# CLKB_clocking_fpga.net
KiCad netlist of a schematic drawn in Altium Designer
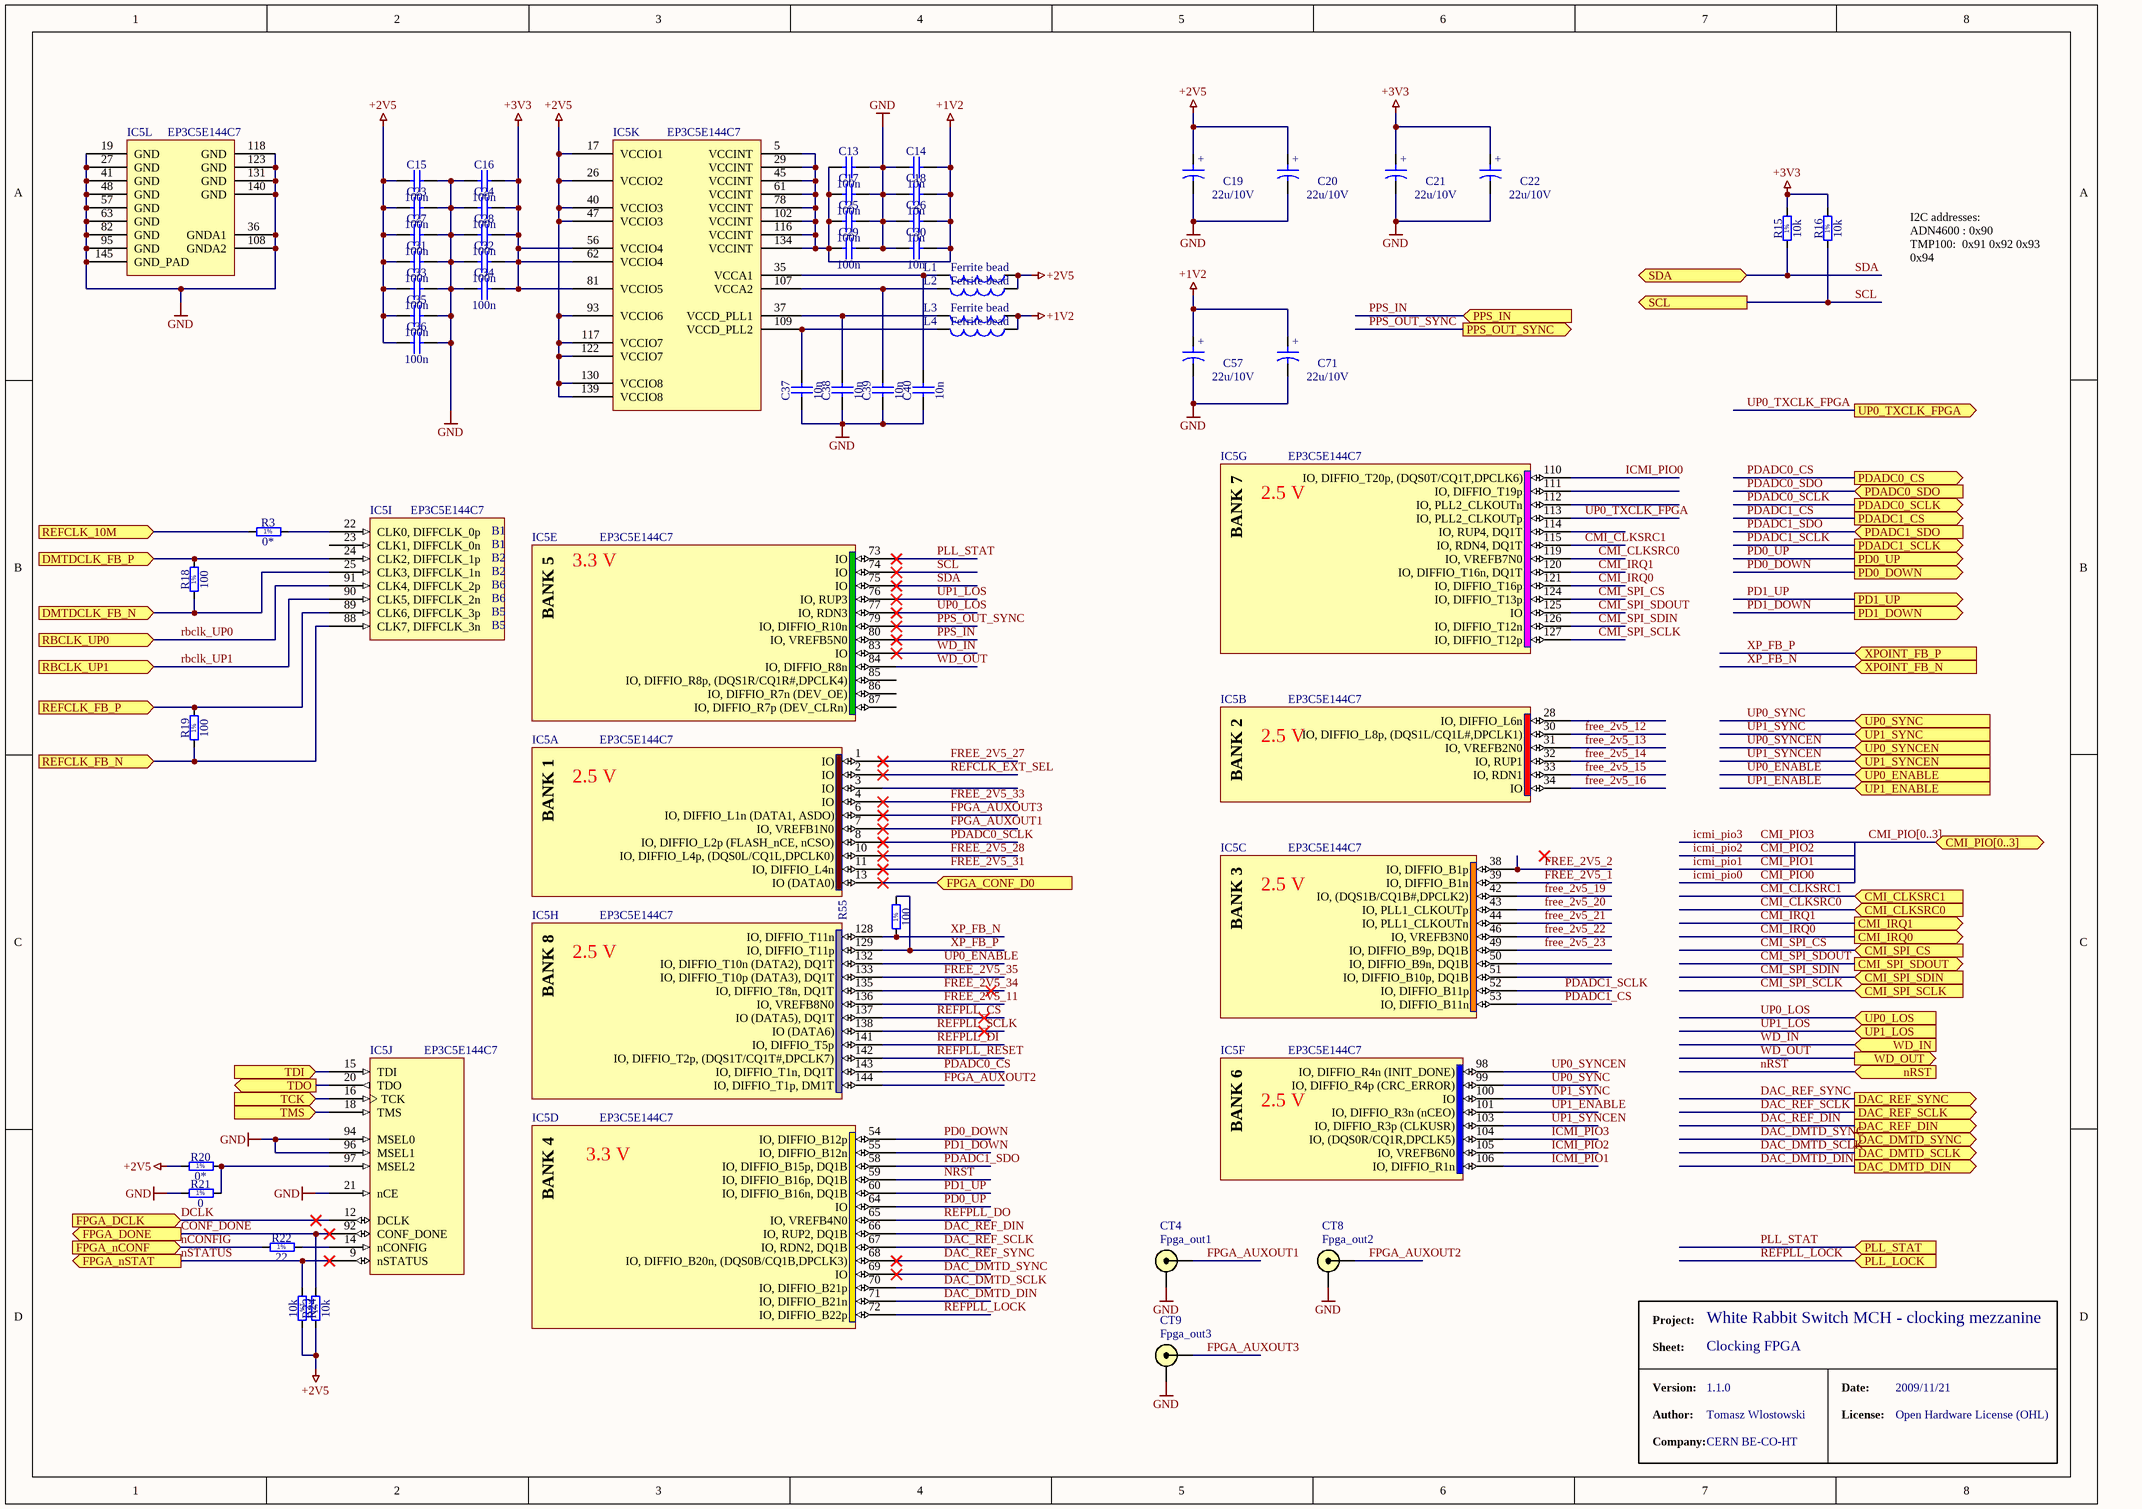
[diagram p0: CLKB_clocking_fpga.SchDoc]

(export (version "E")
  (design (tool "Eeschema 10.0.6"))
  (components
    (comp (ref "C13")
      (value "100n")
      (footprint "CAPC1608X87N")
      (description "Non-polarised capacitor")
      (fields
        (field (name "PART NUMBER") "CC0603_100NF_50V_10%_X7R")
        (field (name "VOLTAGE") "50V")
        (field (name "AUTHOR") "CERN DEM JLC")
      )
      (libsource (lib "Capacitors") (part "Capacitor - non polarized"))
    )
    (comp (ref "C14")
      (value "10n")
      (footprint "CAPC1608X87N")
      (description "Non-polarised capacitor")
      (fields
        (field (name "PART NUMBER") "CC0603_10NF_50V_10%_X7R")
        (field (name "VOLTAGE") "50V")
        (field (name "AUTHOR") "CERN DEM JLC")
      )
      (libsource (lib "Capacitors") (part "Capacitor - non polarized"))
    )
    (comp (ref "C15")
      (value "100n")
      (footprint "CAPC1608X87N")
      (description "Non-polarised capacitor")
      (fields
        (field (name "PART NUMBER") "CC0603_100NF_50V_10%_X7R")
        (field (name "VOLTAGE") "50V")
        (field (name "AUTHOR") "CERN DEM JLC")
      )
      (libsource (lib "Capacitors") (part "Capacitor - non polarized"))
    )
    (comp (ref "C16")
      (value "100n")
      (footprint "CAPC1608X87N")
      (description "Non-polarised capacitor")
      (fields
        (field (name "PART NUMBER") "CC0603_100NF_50V_10%_X7R")
        (field (name "VOLTAGE") "50V")
        (field (name "AUTHOR") "CERN DEM JLC")
      )
      (libsource (lib "Capacitors") (part "Capacitor - non polarized"))
    )
    (comp (ref "C17")
      (value "100n")
      (footprint "CAPC1608X87N")
      (description "Non-polarised capacitor")
      (fields
        (field (name "PART NUMBER") "CC0603_100NF_50V_10%_X7R")
        (field (name "VOLTAGE") "50V")
        (field (name "AUTHOR") "CERN DEM JLC")
      )
      (libsource (lib "Capacitors") (part "Capacitor - non polarized"))
    )
    (comp (ref "C18")
      (value "10n")
      (footprint "CAPC1608X87N")
      (description "Non-polarised capacitor")
      (fields
        (field (name "PART NUMBER") "CC0603_10NF_50V_10%_X7R")
        (field (name "VOLTAGE") "50V")
        (field (name "AUTHOR") "CERN DEM JLC")
      )
      (libsource (lib "Capacitors") (part "Capacitor - non polarized"))
    )
    (comp (ref "C19")
      (value "22u/10V")
      (footprint "CAPMP3216X180N")
      (description "Polarised capacitor")
      (fields
        (field (name "PART NUMBER") "CTE3216-18_22UF_10V_10%")
        (field (name "VOLTAGE") "10V")
        (field (name "AUTHOR") "CERN DEM JLC")
      )
      (libsource (lib "Capacitors") (part "Capacitor - polarized"))
    )
    (comp (ref "C20")
      (value "22u/10V")
      (footprint "CAPMP3216X180N")
      (description "Polarised capacitor")
      (fields
        (field (name "PART NUMBER") "CTE3216-18_22UF_10V_10%")
        (field (name "VOLTAGE") "10V")
        (field (name "AUTHOR") "CERN DEM JLC")
      )
      (libsource (lib "Capacitors") (part "Capacitor - polarized"))
    )
    (comp (ref "C21")
      (value "22u/10V")
      (footprint "CAPMP3216X180N")
      (description "Polarised capacitor")
      (fields
        (field (name "PART NUMBER") "CTE3216-18_22UF_10V_10%")
        (field (name "VOLTAGE") "10V")
        (field (name "AUTHOR") "CERN DEM JLC")
      )
      (libsource (lib "Capacitors") (part "Capacitor - polarized"))
    )
    (comp (ref "C22")
      (value "22u/10V")
      (footprint "CAPMP3216X180N")
      (description "Polarised capacitor")
      (fields
        (field (name "PART NUMBER") "CTE3216-18_22UF_10V_10%")
        (field (name "VOLTAGE") "10V")
        (field (name "AUTHOR") "CERN DEM JLC")
      )
      (libsource (lib "Capacitors") (part "Capacitor - polarized"))
    )
    (comp (ref "C23")
      (value "100n")
      (footprint "CAPC1608X87N")
      (description "Non-polarised capacitor")
      (fields
        (field (name "PART NUMBER") "CC0603_100NF_50V_10%_X7R")
        (field (name "VOLTAGE") "50V")
        (field (name "AUTHOR") "CERN DEM JLC")
      )
      (libsource (lib "Capacitors") (part "Capacitor - non polarized"))
    )
    (comp (ref "C24")
      (value "100n")
      (footprint "CAPC1608X87N")
      (description "Non-polarised capacitor")
      (fields
        (field (name "PART NUMBER") "CC0603_100NF_50V_10%_X7R")
        (field (name "VOLTAGE") "50V")
        (field (name "AUTHOR") "CERN DEM JLC")
      )
      (libsource (lib "Capacitors") (part "Capacitor - non polarized"))
    )
    (comp (ref "C25")
      (value "100n")
      (footprint "CAPC1608X87N")
      (description "Non-polarised capacitor")
      (fields
        (field (name "PART NUMBER") "CC0603_100NF_50V_10%_X7R")
        (field (name "VOLTAGE") "50V")
        (field (name "AUTHOR") "CERN DEM JLC")
      )
      (libsource (lib "Capacitors") (part "Capacitor - non polarized"))
    )
    (comp (ref "C26")
      (value "10n")
      (footprint "CAPC1608X87N")
      (description "Non-polarised capacitor")
      (fields
        (field (name "PART NUMBER") "CC0603_10NF_50V_10%_X7R")
        (field (name "VOLTAGE") "50V")
        (field (name "AUTHOR") "CERN DEM JLC")
      )
      (libsource (lib "Capacitors") (part "Capacitor - non polarized"))
    )
    (comp (ref "C27")
      (value "100n")
      (footprint "CAPC1608X87N")
      (description "Non-polarised capacitor")
      (fields
        (field (name "PART NUMBER") "CC0603_100NF_50V_10%_X7R")
        (field (name "VOLTAGE") "50V")
        (field (name "AUTHOR") "CERN DEM JLC")
      )
      (libsource (lib "Capacitors") (part "Capacitor - non polarized"))
    )
    (comp (ref "C28")
      (value "100n")
      (footprint "CAPC1608X87N")
      (description "Non-polarised capacitor")
      (fields
        (field (name "PART NUMBER") "CC0603_100NF_50V_10%_X7R")
        (field (name "VOLTAGE") "50V")
        (field (name "AUTHOR") "CERN DEM JLC")
      )
      (libsource (lib "Capacitors") (part "Capacitor - non polarized"))
    )
    (comp (ref "C29")
      (value "100n")
      (footprint "CAPC1608X87N")
      (description "Non-polarised capacitor")
      (fields
        (field (name "PART NUMBER") "CC0603_100NF_50V_10%_X7R")
        (field (name "VOLTAGE") "50V")
        (field (name "AUTHOR") "CERN DEM JLC")
      )
      (libsource (lib "Capacitors") (part "Capacitor - non polarized"))
    )
    (comp (ref "C30")
      (value "10n")
      (footprint "CAPC1608X87N")
      (description "Non-polarised capacitor")
      (fields
        (field (name "PART NUMBER") "CC0603_10NF_50V_10%_X7R")
        (field (name "VOLTAGE") "50V")
        (field (name "AUTHOR") "CERN DEM JLC")
      )
      (libsource (lib "Capacitors") (part "Capacitor - non polarized"))
    )
    (comp (ref "C31")
      (value "100n")
      (footprint "CAPC1608X87N")
      (description "Non-polarised capacitor")
      (fields
        (field (name "PART NUMBER") "CC0603_100NF_50V_10%_X7R")
        (field (name "VOLTAGE") "50V")
        (field (name "AUTHOR") "CERN DEM JLC")
      )
      (libsource (lib "Capacitors") (part "Capacitor - non polarized"))
    )
    (comp (ref "C32")
      (value "100n")
      (footprint "CAPC1608X87N")
      (description "Non-polarised capacitor")
      (fields
        (field (name "PART NUMBER") "CC0603_100NF_50V_10%_X7R")
        (field (name "VOLTAGE") "50V")
        (field (name "AUTHOR") "CERN DEM JLC")
      )
      (libsource (lib "Capacitors") (part "Capacitor - non polarized"))
    )
    (comp (ref "C33")
      (value "100n")
      (footprint "CAPC1608X87N")
      (description "Non-polarised capacitor")
      (fields
        (field (name "PART NUMBER") "CC0603_100NF_50V_10%_X7R")
        (field (name "VOLTAGE") "50V")
        (field (name "AUTHOR") "CERN DEM JLC")
      )
      (libsource (lib "Capacitors") (part "Capacitor - non polarized"))
    )
    (comp (ref "C34")
      (value "100n")
      (footprint "CAPC1608X87N")
      (description "Non-polarised capacitor")
      (fields
        (field (name "PART NUMBER") "CC0603_100NF_50V_10%_X7R")
        (field (name "VOLTAGE") "50V")
        (field (name "AUTHOR") "CERN DEM JLC")
      )
      (libsource (lib "Capacitors") (part "Capacitor - non polarized"))
    )
    (comp (ref "C35")
      (value "100n")
      (footprint "CAPC1608X87N")
      (description "Non-polarised capacitor")
      (fields
        (field (name "PART NUMBER") "CC0603_100NF_50V_10%_X7R")
        (field (name "VOLTAGE") "50V")
        (field (name "AUTHOR") "CERN DEM JLC")
      )
      (libsource (lib "Capacitors") (part "Capacitor - non polarized"))
    )
    (comp (ref "C36")
      (value "100n")
      (footprint "CAPC1608X87N")
      (description "Non-polarised capacitor")
      (fields
        (field (name "PART NUMBER") "CC0603_100NF_50V_10%_X7R")
        (field (name "VOLTAGE") "50V")
        (field (name "AUTHOR") "CERN DEM JLC")
      )
      (libsource (lib "Capacitors") (part "Capacitor - non polarized"))
    )
    (comp (ref "C37")
      (value "10n")
      (footprint "CAPC1608X87N")
      (description "Non-polarised capacitor")
      (fields
        (field (name "PART NUMBER") "CC0603_10NF_50V_10%_X7R")
        (field (name "VOLTAGE") "50V")
        (field (name "AUTHOR") "CERN DEM JLC")
      )
      (libsource (lib "Capacitors") (part "Capacitor - non polarized"))
    )
    (comp (ref "C38")
      (value "10n")
      (footprint "CAPC1608X87N")
      (description "Non-polarised capacitor")
      (fields
        (field (name "PART NUMBER") "CC0603_10NF_50V_10%_X7R")
        (field (name "VOLTAGE") "50V")
        (field (name "AUTHOR") "CERN DEM JLC")
      )
      (libsource (lib "Capacitors") (part "Capacitor - non polarized"))
    )
    (comp (ref "C39")
      (value "10n")
      (footprint "CAPC1608X87N")
      (description "Non-polarised capacitor")
      (fields
        (field (name "PART NUMBER") "CC0603_10NF_50V_10%_X7R")
        (field (name "VOLTAGE") "50V")
        (field (name "AUTHOR") "CERN DEM JLC")
      )
      (libsource (lib "Capacitors") (part "Capacitor - non polarized"))
    )
    (comp (ref "C40")
      (value "10n")
      (footprint "CAPC1608X87N")
      (description "Non-polarised capacitor")
      (fields
        (field (name "PART NUMBER") "CC0603_10NF_50V_10%_X7R")
        (field (name "VOLTAGE") "50V")
        (field (name "AUTHOR") "CERN DEM JLC")
      )
      (libsource (lib "Capacitors") (part "Capacitor - non polarized"))
    )
    (comp (ref "C57")
      (value "22u/10V")
      (footprint "CAPMP3216X180N")
      (description "Polarised capacitor")
      (fields
        (field (name "PART NUMBER") "CTE3216-18_22UF_10V_10%")
        (field (name "VOLTAGE") "10V")
        (field (name "AUTHOR") "CERN DEM JLC")
      )
      (libsource (lib "Capacitors") (part "Capacitor - polarized"))
    )
    (comp (ref "C71")
      (value "22u/10V")
      (footprint "CAPMP3216X180N")
      (description "Polarised capacitor")
      (fields
        (field (name "PART NUMBER") "CTE3216-18_22UF_10V_10%")
        (field (name "VOLTAGE") "10V")
        (field (name "AUTHOR") "CERN DEM JLC")
      )
      (libsource (lib "Capacitors") (part "Capacitor - polarized"))
    )
    (comp (ref "CT4")
      (value "Fpga_out1")
      (footprint "CON_UFL_HIROSE_RECEPTACLE")
      (description "UFL connector testpoint")
      (libsource (lib "wr_switch") (part "CON_TESTPOINT_UFL"))
    )
    (comp (ref "CT8")
      (value "Fpga_out2")
      (footprint "CON_UFL_HIROSE_RECEPTACLE")
      (description "UFL connector testpoint")
      (libsource (lib "wr_switch") (part "CON_TESTPOINT_UFL"))
    )
    (comp (ref "CT9")
      (value "Fpga_out3")
      (footprint "CON_UFL_HIROSE_RECEPTACLE")
      (description "UFL connector testpoint")
      (libsource (lib "wr_switch") (part "CON_TESTPOINT_UFL"))
    )
    (comp (ref "IC5")
      (value "EP3C5E144C7")
      (footprint "EQFP144_N")
      (description "Cyclone III Family FPGA, 94 I/O Pins, 4 PLLs, 144-Pin EQFP, Speed Grade 7, Commercial Grade")
      (fields (field (name "PUBLISHER") "Altium Limited"))
      (libsource (lib "wr_switch") (part "EP3C5E144C7"))
    )
    (comp (ref "L1")
      (value "Ferrite bead")
      (footprint "L0603")
      (fields (field (name "PUBLISHER") "Altium Limited"))
      (libsource (lib "Miscellaneous Devices") (part "Inductor"))
    )
    (comp (ref "L2")
      (value "Ferrite bead")
      (footprint "L0603")
      (fields (field (name "PUBLISHER") "Altium Limited"))
      (libsource (lib "Miscellaneous Devices") (part "Inductor"))
    )
    (comp (ref "L3")
      (value "Ferrite bead")
      (footprint "L0603")
      (fields (field (name "PUBLISHER") "Altium Limited"))
      (libsource (lib "Miscellaneous Devices") (part "Inductor"))
    )
    (comp (ref "L4")
      (value "Ferrite bead")
      (footprint "L0603")
      (fields (field (name "PUBLISHER") "Altium Limited"))
      (libsource (lib "Miscellaneous Devices") (part "Inductor"))
    )
    (comp (ref "R3")
      (value "0*")
      (footprint "RESC1608X55N")
      (description "Resistor - 1%")
      (fields
        (field (name "PART NUMBER") "R0603_0R_JUMPER")
        (field (name "MANUFACTURER") "GENERIC")
        (field (name "AUTHOR") "CERN DEM JLC")
      )
      (libsource (lib "Resistors") (part "Resistor - 1%"))
    )
    (comp (ref "R15")
      (value "10k")
      (footprint "RESC1608X55N")
      (description "Resistor - 1%")
      (fields
        (field (name "PART NUMBER") "R0603_10K_1%_0.1W_100PPM")
        (field (name "POWER") "0.1W")
        (field (name "AUTHOR") "CERN DEM JLC")
      )
      (libsource (lib "Resistors") (part "Resistor - 1%"))
    )
    (comp (ref "R16")
      (value "10k")
      (footprint "RESC1608X55N")
      (description "Resistor - 1%")
      (fields
        (field (name "PART NUMBER") "R0603_10K_1%_0.1W_100PPM")
        (field (name "POWER") "0.1W")
        (field (name "AUTHOR") "CERN DEM JLC")
      )
      (libsource (lib "Resistors") (part "Resistor - 1%"))
    )
    (comp (ref "R18")
      (value "100")
      (footprint "RESC1608X55N")
      (description "Resistor - 1%")
      (fields
        (field (name "PART NUMBER") "R0603_100R_1%_0.1W_100PPM")
        (field (name "POWER") "0.1W")
        (field (name "AUTHOR") "CERN DEM JLC")
      )
      (libsource (lib "Resistors") (part "Resistor - 1%"))
    )
    (comp (ref "R19")
      (value "100")
      (footprint "RESC1608X55N")
      (description "Resistor - 1%")
      (fields
        (field (name "PART NUMBER") "R0603_100R_1%_0.1W_100PPM")
        (field (name "POWER") "0.1W")
        (field (name "AUTHOR") "CERN DEM JLC")
      )
      (libsource (lib "Resistors") (part "Resistor - 1%"))
    )
    (comp (ref "R20")
      (value "0*")
      (footprint "RESC1608X55N")
      (description "Resistor - 1%")
      (fields
        (field (name "PART NUMBER") "R0603_0R_JUMPER")
        (field (name "MANUFACTURER") "GENERIC")
        (field (name "AUTHOR") "CERN DEM JLC")
      )
      (libsource (lib "Resistors") (part "Resistor - 1%"))
    )
    (comp (ref "R21")
      (value "0")
      (footprint "RESC1608X55N")
      (description "Resistor - 1%")
      (fields
        (field (name "PART NUMBER") "R0603_0R_JUMPER")
        (field (name "MANUFACTURER") "GENERIC")
        (field (name "AUTHOR") "CERN DEM JLC")
      )
      (libsource (lib "Resistors") (part "Resistor - 1%"))
    )
    (comp (ref "R22")
      (value "22")
      (footprint "RESC1608X55N")
      (description "Resistor - 1%")
      (fields
        (field (name "PART NUMBER") "R0603_22R_1%_0.1W_100PPM")
        (field (name "POWER") "0.1W")
        (field (name "AUTHOR") "CERN DEM JLC")
      )
      (libsource (lib "Resistors") (part "Resistor - 1%"))
    )
    (comp (ref "R23")
      (value "10k")
      (footprint "RESC1608X55N")
      (description "Resistor - 1%")
      (fields
        (field (name "PART NUMBER") "R0603_10K_1%_0.1W_100PPM")
        (field (name "POWER") "0.1W")
        (field (name "AUTHOR") "CERN DEM JLC")
      )
      (libsource (lib "Resistors") (part "Resistor - 1%"))
    )
    (comp (ref "R24")
      (value "10k")
      (footprint "RESC1608X55N")
      (description "Resistor - 1%")
      (fields
        (field (name "PART NUMBER") "R0603_10K_1%_0.1W_100PPM")
        (field (name "POWER") "0.1W")
        (field (name "AUTHOR") "CERN DEM JLC")
      )
      (libsource (lib "Resistors") (part "Resistor - 1%"))
    )
    (comp (ref "R55")
      (value "100")
      (footprint "RESC1608X55N")
      (description "Resistor - 1%")
      (fields
        (field (name "PART NUMBER") "R0603_100R_1%_0.1W_100PPM")
        (field (name "POWER") "0.1W")
        (field (name "AUTHOR") "CERN DEM JLC")
      )
      (libsource (lib "Resistors") (part "Resistor - 1%"))
    )
  )
  (nets
    (net (code "1") (name "+1V2") (class "Default")
      (node (ref "C13") (pin "1") (pinfunction "1_1") (pintype "passive"))
      (node (ref "C14") (pin "2") (pinfunction "2_2") (pintype "passive"))
      (node (ref "C17") (pin "1") (pinfunction "1_1") (pintype "passive"))
      (node (ref "C18") (pin "2") (pinfunction "2_2") (pintype "passive"))
      (node (ref "C25") (pin "1") (pinfunction "1_1") (pintype "passive"))
      (node (ref "C26") (pin "2") (pinfunction "2_2") (pintype "passive"))
      (node (ref "C29") (pin "1") (pinfunction "1_1") (pintype "passive"))
      (node (ref "C30") (pin "2") (pinfunction "2_2") (pintype "passive"))
      (node (ref "C57") (pin "1") (pinfunction "1_1") (pintype "passive"))
      (node (ref "C71") (pin "1") (pinfunction "1_1") (pintype "passive"))
      (node (ref "IC5") (pin "102") (pinfunction "VCCINT_102") (pintype "power_in"))
      (node (ref "IC5") (pin "116") (pinfunction "VCCINT_116") (pintype "power_in"))
      (node (ref "IC5") (pin "134") (pinfunction "VCCINT_134") (pintype "power_in"))
      (node (ref "IC5") (pin "29") (pinfunction "VCCINT_29") (pintype "power_in"))
      (node (ref "IC5") (pin "45") (pinfunction "VCCINT_45") (pintype "power_in"))
      (node (ref "IC5") (pin "5") (pinfunction "VCCINT_5") (pintype "power_in"))
      (node (ref "IC5") (pin "61") (pinfunction "VCCINT_61") (pintype "power_in"))
      (node (ref "IC5") (pin "78") (pinfunction "VCCINT_78") (pintype "power_in"))
      (node (ref "L3") (pin "1") (pinfunction "1_1") (pintype "passive"))
      (node (ref "L4") (pin "1") (pinfunction "1_1") (pintype "passive"))
    )
    (net (code "2") (name "+2V5") (class "Default")
      (node (ref "C15") (pin "1") (pinfunction "1_1") (pintype "passive"))
      (node (ref "C19") (pin "1") (pinfunction "1_1") (pintype "passive"))
      (node (ref "C20") (pin "1") (pinfunction "1_1") (pintype "passive"))
      (node (ref "C23") (pin "1") (pinfunction "1_1") (pintype "passive"))
      (node (ref "C27") (pin "1") (pinfunction "1_1") (pintype "passive"))
      (node (ref "C31") (pin "1") (pinfunction "1_1") (pintype "passive"))
      (node (ref "C33") (pin "1") (pinfunction "1_1") (pintype "passive"))
      (node (ref "C35") (pin "1") (pinfunction "1_1") (pintype "passive"))
      (node (ref "C36") (pin "1") (pinfunction "1_1") (pintype "passive"))
      (node (ref "IC5") (pin "117") (pinfunction "VCCIO7_117") (pintype "power_in"))
      (node (ref "IC5") (pin "122") (pinfunction "VCCIO7_122") (pintype "power_in"))
      (node (ref "IC5") (pin "130") (pinfunction "VCCIO8_130") (pintype "power_in"))
      (node (ref "IC5") (pin "139") (pinfunction "VCCIO8_139") (pintype "power_in"))
      (node (ref "IC5") (pin "17") (pinfunction "VCCIO1_17") (pintype "power_in"))
      (node (ref "IC5") (pin "26") (pinfunction "VCCIO2_26") (pintype "power_in"))
      (node (ref "IC5") (pin "40") (pinfunction "VCCIO3_40") (pintype "power_in"))
      (node (ref "IC5") (pin "47") (pinfunction "VCCIO3_47") (pintype "power_in"))
      (node (ref "IC5") (pin "93") (pinfunction "VCCIO6_93") (pintype "power_in"))
      (node (ref "L1") (pin "1") (pinfunction "1_1") (pintype "passive"))
      (node (ref "L2") (pin "1") (pinfunction "1_1") (pintype "passive"))
      (node (ref "R20") (pin "1") (pinfunction "1_1") (pintype "passive"))
      (node (ref "R23") (pin "1") (pinfunction "1_1") (pintype "passive"))
      (node (ref "R24") (pin "2") (pinfunction "2_2") (pintype "passive"))
    )
    (net (code "3") (name "+3V3") (class "Default")
      (node (ref "C16") (pin "2") (pinfunction "2_2") (pintype "passive"))
      (node (ref "C21") (pin "1") (pinfunction "1_1") (pintype "passive"))
      (node (ref "C22") (pin "1") (pinfunction "1_1") (pintype "passive"))
      (node (ref "C24") (pin "2") (pinfunction "2_2") (pintype "passive"))
      (node (ref "C28") (pin "2") (pinfunction "2_2") (pintype "passive"))
      (node (ref "C32") (pin "2") (pinfunction "2_2") (pintype "passive"))
      (node (ref "C34") (pin "2") (pinfunction "2_2") (pintype "passive"))
      (node (ref "IC5") (pin "56") (pinfunction "VCCIO4_56") (pintype "power_in"))
      (node (ref "IC5") (pin "62") (pinfunction "VCCIO4_62") (pintype "power_in"))
      (node (ref "IC5") (pin "81") (pinfunction "VCCIO5_81") (pintype "power_in"))
      (node (ref "R15") (pin "2") (pinfunction "2_2") (pintype "passive"))
      (node (ref "R16") (pin "2") (pinfunction "2_2") (pintype "passive"))
    )
    (net (code "4") (name "/CMI_CLKSRC0") (class "Default")
      (node (ref "IC5") (pin "119") (pinfunction "IO,_VREFB7N0_119") (pintype "bidirectional"))
    )
    (net (code "5") (name "/CMI_CLKSRC1") (class "Default")
      (node (ref "IC5") (pin "115") (pinfunction "IO,_RDN4,_DQ1T_115") (pintype "bidirectional"))
    )
    (net (code "6") (name "/CMI_IRQ0") (class "Default")
      (node (ref "IC5") (pin "121") (pinfunction "IO,_DIFFIO_T16p_121") (pintype "bidirectional"))
    )
    (net (code "7") (name "/CMI_IRQ1") (class "Default")
      (node (ref "IC5") (pin "120") (pinfunction "IO,_DIFFIO_T16n,_DQ1T_120") (pintype "bidirectional"))
    )
    (net (code "13") (name "/CMI_SPI_CS") (class "Default")
      (node (ref "IC5") (pin "124") (pinfunction "IO,_DIFFIO_T13p_124") (pintype "bidirectional"))
    )
    (net (code "14") (name "/CMI_SPI_SCLK") (class "Default")
      (node (ref "IC5") (pin "127") (pinfunction "IO,_DIFFIO_T12p_127") (pintype "bidirectional"))
    )
    (net (code "15") (name "/CMI_SPI_SDIN") (class "Default")
      (node (ref "IC5") (pin "126") (pinfunction "IO,_DIFFIO_T12n_126") (pintype "bidirectional"))
    )
    (net (code "16") (name "/CMI_SPI_SDOUT") (class "Default")
      (node (ref "IC5") (pin "125") (pinfunction "IO_125") (pintype "bidirectional"))
    )
    (net (code "17") (name "/CONF_DONE") (class "Default")
      (node (ref "IC5") (pin "92") (pinfunction "CONF_DONE_92") (pintype "bidirectional"))
      (node (ref "R23") (pin "2") (pinfunction "2_2") (pintype "passive"))
    )
    (net (code "18") (name "/DAC_DMTD_DIN") (class "Default")
      (node (ref "IC5") (pin "71") (pinfunction "IO,_DIFFIO_B21n_71") (pintype "bidirectional"))
    )
    (net (code "19") (name "/DAC_DMTD_SCLK") (class "Default")
      (node (ref "IC5") (pin "70") (pinfunction "IO,_DIFFIO_B21p_70") (pintype "bidirectional"))
    )
    (net (code "20") (name "/DAC_DMTD_SYNC") (class "Default")
      (node (ref "IC5") (pin "69") (pinfunction "IO_69") (pintype "bidirectional+no_connect"))
    )
    (net (code "21") (name "/DAC_REF_DIN") (class "Default")
      (node (ref "IC5") (pin "66") (pinfunction "IO,_RUP2,_DQ1B_66") (pintype "bidirectional"))
    )
    (net (code "22") (name "/DAC_REF_SCLK") (class "Default")
      (node (ref "IC5") (pin "67") (pinfunction "IO,_RDN2,_DQ1B_67") (pintype "bidirectional"))
    )
    (net (code "23") (name "/DAC_REF_SYNC") (class "Default")
      (node (ref "IC5") (pin "68") (pinfunction "IO,_DIFFIO_B20n,_(DQS0B/CQ1B,DPCLK3)_68") (pintype "bidirectional+no_connect"))
    )
    (net (code "24") (name "/DCLK") (class "Default")
      (node (ref "IC5") (pin "12") (pinfunction "DCLK_12") (pintype "bidirectional"))
    )
    (net (code "25") (name "/DMTDCLK_FB_N") (class "Default")
      (node (ref "IC5") (pin "25") (pinfunction "CLK3,_DIFFCLK_1n_25") (pintype "input"))
      (node (ref "R18") (pin "1") (pinfunction "1_1") (pintype "passive"))
    )
    (net (code "26") (name "/DMTDCLK_FB_P") (class "Default")
      (node (ref "IC5") (pin "24") (pinfunction "CLK2,_DIFFCLK_1p_24") (pintype "input"))
      (node (ref "R18") (pin "2") (pinfunction "2_2") (pintype "passive"))
    )
    (net (code "27") (name "/FPGA_AUXOUT1") (class "Default")
      (node (ref "CT4") (pin "1") (pintype "passive"))
      (node (ref "IC5") (pin "7") (pinfunction "IO,_VREFB1N0_7") (pintype "bidirectional"))
    )
    (net (code "28") (name "/FPGA_AUXOUT2") (class "Default")
      (node (ref "CT8") (pin "1") (pintype "passive"))
      (node (ref "IC5") (pin "144") (pinfunction "IO,_DIFFIO_T1p,_DM1T_144") (pintype "bidirectional"))
    )
    (net (code "29") (name "/FPGA_AUXOUT3") (class "Default")
      (node (ref "CT9") (pin "1") (pintype "passive"))
      (node (ref "IC5") (pin "6") (pinfunction "IO,_DIFFIO_L1n_(DATA1,_ASDO)_6") (pintype "bidirectional"))
    )
    (net (code "30") (name "/FPGA_CONF_D0") (class "Default")
      (node (ref "IC5") (pin "13") (pinfunction "IO_(DATA0)_13") (pintype "bidirectional+no_connect"))
    )
    (net (code "31") (name "/FREE_2V5_1") (class "Default")
      (node (ref "IC5") (pin "39") (pinfunction "IO,_DIFFIO_B1n_39") (pintype "bidirectional"))
    )
    (net (code "32") (name "/FREE_2V5_2") (class "Default")
      (node (ref "IC5") (pin "38") (pinfunction "IO,_DIFFIO_B1p_38") (pintype "bidirectional"))
    )
    (net (code "33") (name "/FREE_2V5_11") (class "Default")
      (node (ref "IC5") (pin "136") (pinfunction "IO,_VREFB8N0_136") (pintype "bidirectional"))
    )
    (net (code "34") (name "/FREE_2V5_27") (class "Default")
      (node (ref "IC5") (pin "1") (pinfunction "IO_1") (pintype "bidirectional+no_connect"))
    )
    (net (code "35") (name "/FREE_2V5_28") (class "Default")
      (node (ref "IC5") (pin "10") (pinfunction "IO,_DIFFIO_L4p,_(DQS0L/CQ1L,DPCLK0)_10") (pintype "bidirectional+no_connect"))
    )
    (net (code "36") (name "/FREE_2V5_31") (class "Default")
      (node (ref "IC5") (pin "11") (pinfunction "IO,_DIFFIO_L4n_11") (pintype "bidirectional+no_connect"))
    )
    (net (code "37") (name "/FREE_2V5_33") (class "Default")
      (node (ref "IC5") (pin "4") (pinfunction "IO_4") (pintype "bidirectional+no_connect"))
    )
    (net (code "38") (name "/FREE_2V5_34") (class "Default")
      (node (ref "IC5") (pin "135") (pinfunction "IO,_DIFFIO_T8n,_DQ1T_135") (pintype "bidirectional"))
    )
    (net (code "39") (name "/FREE_2V5_35") (class "Default")
      (node (ref "IC5") (pin "133") (pinfunction "IO,_DIFFIO_T10p_(DATA3),_DQ1T_133") (pintype "bidirectional"))
    )
    (net (code "40") (name "/ICMI_PIO0") (class "Default")
      (node (ref "IC5") (pin "110") (pinfunction "IO,_DIFFIO_T20p,_(DQS0T/CQ1T,DPCLK6)_110") (pintype "bidirectional"))
    )
    (net (code "41") (name "/ICMI_PIO1") (class "Default")
      (node (ref "IC5") (pin "106") (pinfunction "IO,_DIFFIO_R1n_106") (pintype "bidirectional"))
    )
    (net (code "42") (name "/ICMI_PIO2") (class "Default")
      (node (ref "IC5") (pin "105") (pinfunction "IO,_VREFB6N0_105") (pintype "bidirectional"))
    )
    (net (code "43") (name "/ICMI_PIO3") (class "Default")
      (node (ref "IC5") (pin "104") (pinfunction "IO,_(DQS0R/CQ1R,DPCLK5)_104") (pintype "bidirectional"))
    )
    (net (code "44") (name "/NRST") (class "Default")
      (node (ref "IC5") (pin "59") (pinfunction "IO,_DIFFIO_B16p,_DQ1B_59") (pintype "bidirectional"))
    )
    (net (code "45") (name "/PD0_DOWN") (class "Default")
      (node (ref "IC5") (pin "54") (pinfunction "IO,_DIFFIO_B12p_54") (pintype "bidirectional"))
    )
    (net (code "46") (name "/PD0_UP") (class "Default")
      (node (ref "IC5") (pin "64") (pinfunction "IO_64") (pintype "bidirectional"))
    )
    (net (code "47") (name "/PD1_DOWN") (class "Default")
      (node (ref "IC5") (pin "55") (pinfunction "IO,_DIFFIO_B12n_55") (pintype "bidirectional"))
    )
    (net (code "48") (name "/PD1_UP") (class "Default")
      (node (ref "IC5") (pin "60") (pinfunction "IO,_DIFFIO_B16n,_DQ1B_60") (pintype "bidirectional"))
    )
    (net (code "49") (name "/PDADC0_CS") (class "Default")
      (node (ref "IC5") (pin "143") (pinfunction "IO,_DIFFIO_T1n,_DQ1T_143") (pintype "bidirectional"))
    )
    (net (code "50") (name "/PDADC0_SCLK") (class "Default")
      (node (ref "IC5") (pin "8") (pinfunction "IO,_DIFFIO_L2p_(FLASH_nCE,_nCSO)_8") (pintype "bidirectional+no_connect"))
    )
    (net (code "52") (name "/PDADC1_CS") (class "Default")
      (node (ref "IC5") (pin "53") (pinfunction "IO,_DIFFIO_B11n_53") (pintype "bidirectional"))
    )
    (net (code "53") (name "/PDADC1_SCLK") (class "Default")
      (node (ref "IC5") (pin "52") (pinfunction "IO,_DIFFIO_B11p_52") (pintype "bidirectional"))
    )
    (net (code "54") (name "/PDADC1_SDO") (class "Default")
      (node (ref "IC5") (pin "58") (pinfunction "IO,_DIFFIO_B15p,_DQ1B_58") (pintype "bidirectional"))
    )
    (net (code "55") (name "/PLL_STAT") (class "Default")
      (node (ref "IC5") (pin "73") (pinfunction "IO_73") (pintype "bidirectional+no_connect"))
    )
    (net (code "56") (name "/PPS_IN") (class "Default")
      (node (ref "IC5") (pin "80") (pinfunction "IO,_VREFB5N0_80") (pintype "bidirectional+no_connect"))
    )
    (net (code "57") (name "/PPS_OUT_SYNC") (class "Default")
      (node (ref "IC5") (pin "79") (pinfunction "IO,_DIFFIO_R10n_79") (pintype "bidirectional+no_connect"))
    )
    (net (code "58") (name "/REFCLK_10M") (class "Default")
      (node (ref "R3") (pin "1") (pinfunction "1_1") (pintype "passive"))
    )
    (net (code "59") (name "/REFCLK_EXT_SEL") (class "Default")
      (node (ref "IC5") (pin "2") (pinfunction "IO_2") (pintype "bidirectional+no_connect"))
    )
    (net (code "60") (name "/REFCLK_FB_N") (class "Default")
      (node (ref "IC5") (pin "88") (pinfunction "CLK7,_DIFFCLK_3n_88") (pintype "input"))
      (node (ref "R19") (pin "1") (pinfunction "1_1") (pintype "passive"))
    )
    (net (code "61") (name "/REFCLK_FB_P") (class "Default")
      (node (ref "IC5") (pin "89") (pinfunction "CLK6,_DIFFCLK_3p_89") (pintype "input"))
      (node (ref "R19") (pin "2") (pinfunction "2_2") (pintype "passive"))
    )
    (net (code "62") (name "/REFPLL_CS") (class "Default")
      (node (ref "IC5") (pin "137") (pinfunction "IO_(DATA5),_DQ1T_137") (pintype "bidirectional"))
    )
    (net (code "63") (name "/REFPLL_DI") (class "Default")
      (node (ref "IC5") (pin "141") (pinfunction "IO,_DIFFIO_T5p_141") (pintype "bidirectional"))
    )
    (net (code "64") (name "/REFPLL_DO") (class "Default")
      (node (ref "IC5") (pin "65") (pinfunction "IO,_VREFB4N0_65") (pintype "bidirectional"))
    )
    (net (code "65") (name "/REFPLL_LOCK") (class "Default")
      (node (ref "IC5") (pin "72") (pinfunction "IO,_DIFFIO_B22p_72") (pintype "bidirectional"))
    )
    (net (code "66") (name "/REFPLL_RESET") (class "Default")
      (node (ref "IC5") (pin "142") (pinfunction "IO,_DIFFIO_T2p,_(DQS1T/CQ1T#,DPCLK7)_142") (pintype "bidirectional"))
    )
    (net (code "67") (name "/REFPLL_SCLK") (class "Default")
      (node (ref "IC5") (pin "138") (pinfunction "IO_(DATA6)_138") (pintype "bidirectional"))
    )
    (net (code "68") (name "/SCL") (class "Default")
      (node (ref "IC5") (pin "74") (pinfunction "IO_74") (pintype "bidirectional"))
      (node (ref "R16") (pin "1") (pinfunction "1_1") (pintype "passive"))
    )
    (net (code "69") (name "/SDA") (class "Default")
      (node (ref "IC5") (pin "75") (pinfunction "IO_75") (pintype "bidirectional"))
      (node (ref "R15") (pin "1") (pinfunction "1_1") (pintype "passive"))
    )
    (net (code "70") (name "/TCK") (class "Default")
      (node (ref "IC5") (pin "16") (pinfunction "TCK_16") (pintype "input"))
    )
    (net (code "71") (name "/TDI") (class "Default")
      (node (ref "IC5") (pin "15") (pinfunction "TDI_15") (pintype "input"))
    )
    (net (code "72") (name "/TDO") (class "Default")
      (node (ref "IC5") (pin "20") (pinfunction "TDO_20") (pintype "output"))
    )
    (net (code "73") (name "/TMS") (class "Default")
      (node (ref "IC5") (pin "18") (pinfunction "TMS_18") (pintype "input"))
    )
    (net (code "74") (name "/UP0_ENABLE") (class "Default")
      (node (ref "IC5") (pin "132") (pinfunction "IO,_DIFFIO_T10n_(DATA2),_DQ1T_132") (pintype "bidirectional"))
    )
    (net (code "75") (name "/UP0_LOS") (class "Default")
      (node (ref "IC5") (pin "77") (pinfunction "IO,_RDN3_77") (pintype "bidirectional+no_connect"))
    )
    (net (code "76") (name "/UP0_SYNC") (class "Default")
      (node (ref "IC5") (pin "99") (pinfunction "IO,_DIFFIO_R4p_(CRC_ERROR)_99") (pintype "bidirectional"))
    )
    (net (code "77") (name "/UP0_SYNCEN") (class "Default")
      (node (ref "IC5") (pin "98") (pinfunction "IO,_DIFFIO_R4n_(INIT_DONE)_98") (pintype "bidirectional"))
    )
    (net (code "78") (name "/UP0_TXCLK_FPGA") (class "Default")
      (node (ref "IC5") (pin "113") (pinfunction "IO,_PLL2_CLKOUTp_113") (pintype "bidirectional"))
    )
    (net (code "79") (name "/UP1_ENABLE") (class "Default")
      (node (ref "IC5") (pin "101") (pinfunction "IO,_DIFFIO_R3n_(nCEO)_101") (pintype "bidirectional"))
    )
    (net (code "80") (name "/UP1_LOS") (class "Default")
      (node (ref "IC5") (pin "76") (pinfunction "IO,_RUP3_76") (pintype "bidirectional+no_connect"))
    )
    (net (code "81") (name "/UP1_SYNC") (class "Default")
      (node (ref "IC5") (pin "100") (pinfunction "IO_100") (pintype "bidirectional"))
    )
    (net (code "82") (name "/UP1_SYNCEN") (class "Default")
      (node (ref "IC5") (pin "103") (pinfunction "IO,_DIFFIO_R3p_(CLKUSR)_103") (pintype "bidirectional"))
    )
    (net (code "83") (name "/WD_IN") (class "Default")
      (node (ref "IC5") (pin "83") (pinfunction "IO_83") (pintype "bidirectional+no_connect"))
    )
    (net (code "84") (name "/WD_OUT") (class "Default")
      (node (ref "IC5") (pin "84") (pinfunction "IO,_DIFFIO_R8n_84") (pintype "bidirectional"))
    )
    (net (code "85") (name "/XP_FB_N") (class "Default")
      (node (ref "IC5") (pin "128") (pinfunction "IO,_DIFFIO_T11n_128") (pintype "bidirectional"))
      (node (ref "R55") (pin "1") (pinfunction "1_1") (pintype "passive"))
    )
    (net (code "86") (name "/XP_FB_P") (class "Default")
      (node (ref "IC5") (pin "129") (pinfunction "IO,_DIFFIO_T11p_129") (pintype "bidirectional"))
      (node (ref "R55") (pin "2") (pinfunction "2_2") (pintype "passive"))
    )
    (net (code "87") (name "/free_2v5_12") (class "Default")
      (node (ref "IC5") (pin "30") (pinfunction "IO,_DIFFIO_L8p,_(DQS1L/CQ1L#,DPCLK1)_30") (pintype "bidirectional"))
    )
    (net (code "88") (name "/free_2v5_13") (class "Default")
      (node (ref "IC5") (pin "31") (pinfunction "IO,_VREFB2N0_31") (pintype "bidirectional"))
    )
    (net (code "89") (name "/free_2v5_14") (class "Default")
      (node (ref "IC5") (pin "32") (pinfunction "IO,_RUP1_32") (pintype "bidirectional"))
    )
    (net (code "90") (name "/free_2v5_15") (class "Default")
      (node (ref "IC5") (pin "33") (pinfunction "IO,_RDN1_33") (pintype "bidirectional"))
    )
    (net (code "91") (name "/free_2v5_16") (class "Default")
      (node (ref "IC5") (pin "34") (pinfunction "IO_34") (pintype "bidirectional"))
    )
    (net (code "92") (name "/free_2v5_19") (class "Default")
      (node (ref "IC5") (pin "42") (pinfunction "IO,_(DQS1B/CQ1B#,DPCLK2)_42") (pintype "bidirectional"))
    )
    (net (code "93") (name "/free_2v5_20") (class "Default")
      (node (ref "IC5") (pin "43") (pinfunction "IO,_PLL1_CLKOUTp_43") (pintype "bidirectional"))
    )
    (net (code "94") (name "/free_2v5_21") (class "Default")
      (node (ref "IC5") (pin "44") (pinfunction "IO,_PLL1_CLKOUTn_44") (pintype "bidirectional"))
    )
    (net (code "95") (name "/free_2v5_22") (class "Default")
      (node (ref "IC5") (pin "46") (pinfunction "IO,_VREFB3N0_46") (pintype "bidirectional"))
    )
    (net (code "96") (name "/free_2v5_23") (class "Default")
      (node (ref "IC5") (pin "49") (pinfunction "IO,_DIFFIO_B9p,_DQ1B_49") (pintype "bidirectional"))
    )
    (net (code "97") (name "/nCONFIG") (class "Default")
      (node (ref "R22") (pin "1") (pinfunction "1_1") (pintype "passive"))
    )
    (net (code "99") (name "/nSTATUS") (class "Default")
      (node (ref "IC5") (pin "9") (pinfunction "nSTATUS_9") (pintype "bidirectional"))
      (node (ref "R24") (pin "1") (pinfunction "1_1") (pintype "passive"))
    )
    (net (code "100") (name "/rbclk_UP0") (class "Default")
      (node (ref "IC5") (pin "91") (pinfunction "CLK4,_DIFFCLK_2p_91") (pintype "input"))
    )
    (net (code "101") (name "/rbclk_UP1") (class "Default")
      (node (ref "IC5") (pin "90") (pinfunction "CLK5,_DIFFCLK_2n_90") (pintype "input"))
    )
    (net (code "102") (name "GND") (class "Default")
      (node (ref "C13") (pin "2") (pinfunction "2_2") (pintype "passive"))
      (node (ref "C14") (pin "1") (pinfunction "1_1") (pintype "passive"))
      (node (ref "C15") (pin "2") (pinfunction "2_2") (pintype "passive"))
      (node (ref "C16") (pin "1") (pinfunction "1_1") (pintype "passive"))
      (node (ref "C17") (pin "2") (pinfunction "2_2") (pintype "passive"))
      (node (ref "C18") (pin "1") (pinfunction "1_1") (pintype "passive"))
      (node (ref "C19") (pin "2") (pinfunction "2_2") (pintype "passive"))
      (node (ref "C20") (pin "2") (pinfunction "2_2") (pintype "passive"))
      (node (ref "C21") (pin "2") (pinfunction "2_2") (pintype "passive"))
      (node (ref "C22") (pin "2") (pinfunction "2_2") (pintype "passive"))
      (node (ref "C23") (pin "2") (pinfunction "2_2") (pintype "passive"))
      (node (ref "C24") (pin "1") (pinfunction "1_1") (pintype "passive"))
      (node (ref "C25") (pin "2") (pinfunction "2_2") (pintype "passive"))
      (node (ref "C26") (pin "1") (pinfunction "1_1") (pintype "passive"))
      (node (ref "C27") (pin "2") (pinfunction "2_2") (pintype "passive"))
      (node (ref "C28") (pin "1") (pinfunction "1_1") (pintype "passive"))
      (node (ref "C29") (pin "2") (pinfunction "2_2") (pintype "passive"))
      (node (ref "C30") (pin "1") (pinfunction "1_1") (pintype "passive"))
      (node (ref "C31") (pin "2") (pinfunction "2_2") (pintype "passive"))
      (node (ref "C32") (pin "1") (pinfunction "1_1") (pintype "passive"))
      (node (ref "C33") (pin "2") (pinfunction "2_2") (pintype "passive"))
      (node (ref "C34") (pin "1") (pinfunction "1_1") (pintype "passive"))
      (node (ref "C35") (pin "2") (pinfunction "2_2") (pintype "passive"))
      (node (ref "C36") (pin "2") (pinfunction "2_2") (pintype "passive"))
      (node (ref "C37") (pin "1") (pinfunction "1_1") (pintype "passive"))
      (node (ref "C38") (pin "1") (pinfunction "1_1") (pintype "passive"))
      (node (ref "C39") (pin "1") (pinfunction "1_1") (pintype "passive"))
      (node (ref "C40") (pin "1") (pinfunction "1_1") (pintype "passive"))
      (node (ref "C57") (pin "2") (pinfunction "2_2") (pintype "passive"))
      (node (ref "C71") (pin "2") (pinfunction "2_2") (pintype "passive"))
      (node (ref "CT4") (pin "2") (pintype "passive"))
      (node (ref "CT8") (pin "2") (pintype "passive"))
      (node (ref "CT9") (pin "2") (pintype "passive"))
      (node (ref "IC5") (pin "108") (pinfunction "GNDA2_108") (pintype "power_in"))
      (node (ref "IC5") (pin "118") (pinfunction "GND_118") (pintype "power_in"))
      (node (ref "IC5") (pin "123") (pinfunction "GND_123") (pintype "power_in"))
      (node (ref "IC5") (pin "131") (pinfunction "GND_131") (pintype "power_in"))
      (node (ref "IC5") (pin "140") (pinfunction "GND_140") (pintype "power_in"))
      (node (ref "IC5") (pin "145") (pinfunction "GND_PAD_145") (pintype "power_in"))
      (node (ref "IC5") (pin "19") (pinfunction "GND_19") (pintype "power_in"))
      (node (ref "IC5") (pin "21") (pinfunction "nCE_21") (pintype "input"))
      (node (ref "IC5") (pin "27") (pinfunction "GND_27") (pintype "power_in"))
      (node (ref "IC5") (pin "36") (pinfunction "GNDA1_36") (pintype "power_in"))
      (node (ref "IC5") (pin "41") (pinfunction "GND_41") (pintype "power_in"))
      (node (ref "IC5") (pin "48") (pinfunction "GND_48") (pintype "power_in"))
      (node (ref "IC5") (pin "57") (pinfunction "GND_57") (pintype "power_in"))
      (node (ref "IC5") (pin "63") (pinfunction "GND_63") (pintype "power_in"))
      (node (ref "IC5") (pin "82") (pinfunction "GND_82") (pintype "power_in"))
      (node (ref "IC5") (pin "94") (pinfunction "MSEL0_94") (pintype "input"))
      (node (ref "IC5") (pin "95") (pinfunction "GND_95") (pintype "power_in"))
      (node (ref "IC5") (pin "96") (pinfunction "MSEL1_96") (pintype "input"))
      (node (ref "R21") (pin "1") (pinfunction "1_1") (pintype "passive"))
    )
    (net (code "103") (name "Net-(IC5I-CLK0,_DIFFCLK_0p)") (class "Default")
      (node (ref "IC5") (pin "22") (pinfunction "CLK0,_DIFFCLK_0p_22") (pintype "input"))
      (node (ref "R3") (pin "2") (pinfunction "2_2") (pintype "passive"))
    )
    (net (code "104") (name "Net-(IC5J-MSEL2)") (class "Default")
      (node (ref "IC5") (pin "97") (pinfunction "MSEL2_97") (pintype "input"))
      (node (ref "R20") (pin "2") (pinfunction "2_2") (pintype "passive"))
      (node (ref "R21") (pin "2") (pinfunction "2_2") (pintype "passive"))
    )
    (net (code "105") (name "Net-(IC5J-nCONFIG)") (class "Default")
      (node (ref "IC5") (pin "14") (pinfunction "nCONFIG_14") (pintype "input"))
      (node (ref "R22") (pin "2") (pinfunction "2_2") (pintype "passive"))
    )
    (net (code "106") (name "Net-(IC5K-VCCA1)") (class "Default")
      (node (ref "C40") (pin "2") (pinfunction "2_2") (pintype "passive"))
      (node (ref "IC5") (pin "35") (pinfunction "VCCA1_35") (pintype "power_in"))
      (node (ref "L1") (pin "2") (pinfunction "2_2") (pintype "passive"))
    )
    (net (code "107") (name "Net-(IC5K-VCCA2)") (class "Default")
      (node (ref "C39") (pin "2") (pinfunction "2_2") (pintype "passive"))
      (node (ref "IC5") (pin "107") (pinfunction "VCCA2_107") (pintype "power_in"))
      (node (ref "L2") (pin "2") (pinfunction "2_2") (pintype "passive"))
    )
    (net (code "108") (name "Net-(IC5K-VCCD_PLL1)") (class "Default")
      (node (ref "C38") (pin "2") (pinfunction "2_2") (pintype "passive"))
      (node (ref "IC5") (pin "37") (pinfunction "VCCD_PLL1_37") (pintype "power_in"))
      (node (ref "L3") (pin "2") (pinfunction "2_2") (pintype "passive"))
    )
    (net (code "109") (name "Net-(IC5K-VCCD_PLL2)") (class "Default")
      (node (ref "C37") (pin "2") (pinfunction "2_2") (pintype "passive"))
      (node (ref "IC5") (pin "109") (pinfunction "VCCD_PLL2_109") (pintype "power_in"))
      (node (ref "L4") (pin "2") (pinfunction "2_2") (pintype "passive"))
    )
    (net (code "110") (name "unconnected-(IC5A-IO-Pad3)") (class "Default")
      (node (ref "IC5") (pin "3") (pinfunction "IO_3") (pintype "bidirectional"))
    )
    (net (code "111") (name "unconnected-(IC5B-IO,_DIFFIO_L6n-Pad28)") (class "Default")
      (node (ref "IC5") (pin "28") (pinfunction "IO,_DIFFIO_L6n_28") (pintype "bidirectional"))
    )
    (net (code "112") (name "unconnected-(IC5C-IO,_DIFFIO_B9n,_DQ1B-Pad50)") (class "Default")
      (node (ref "IC5") (pin "50") (pinfunction "IO,_DIFFIO_B9n,_DQ1B_50") (pintype "bidirectional"))
    )
    (net (code "113") (name "unconnected-(IC5C-IO,_DIFFIO_B10p,_DQ1B-Pad51)") (class "Default")
      (node (ref "IC5") (pin "51") (pinfunction "IO,_DIFFIO_B10p,_DQ1B_51") (pintype "bidirectional"))
    )
    (net (code "114") (name "unconnected-(IC5E-IO,_DIFFIO_R7n_(DEV_OE)-Pad86)") (class "Default")
      (node (ref "IC5") (pin "86") (pinfunction "IO,_DIFFIO_R7n_(DEV_OE)_86") (pintype "bidirectional"))
    )
    (net (code "115") (name "unconnected-(IC5E-IO,_DIFFIO_R7p_(DEV_CLRn)-Pad87)") (class "Default")
      (node (ref "IC5") (pin "87") (pinfunction "IO,_DIFFIO_R7p_(DEV_CLRn)_87") (pintype "bidirectional"))
    )
    (net (code "116") (name "unconnected-(IC5E-IO,_DIFFIO_R8p,_(DQS1R{slash}CQ1R#,DPCLK4)-Pad85)") (class "Default")
      (node (ref "IC5") (pin "85") (pinfunction "IO,_DIFFIO_R8p,_(DQS1R/CQ1R#,DPCLK4)_85") (pintype "bidirectional"))
    )
    (net (code "117") (name "unconnected-(IC5G-IO,_DIFFIO_T19p-Pad111)") (class "Default")
      (node (ref "IC5") (pin "111") (pinfunction "IO,_DIFFIO_T19p_111") (pintype "bidirectional"))
    )
    (net (code "118") (name "unconnected-(IC5G-IO,_PLL2_CLKOUTn-Pad112)") (class "Default")
      (node (ref "IC5") (pin "112") (pinfunction "IO,_PLL2_CLKOUTn_112") (pintype "bidirectional"))
    )
    (net (code "119") (name "unconnected-(IC5G-IO,_RUP4,_DQ1T-Pad114)") (class "Default")
      (node (ref "IC5") (pin "114") (pinfunction "IO,_RUP4,_DQ1T_114") (pintype "bidirectional"))
    )
    (net (code "120") (name "unconnected-(IC5I-CLK1,_DIFFCLK_0n-Pad23)") (class "Default")
      (node (ref "IC5") (pin "23") (pinfunction "CLK1,_DIFFCLK_0n_23") (pintype "input"))
    )
  )
)
